# bikealarm.net
KiCad netlist of a schematic drawn in EAGLE
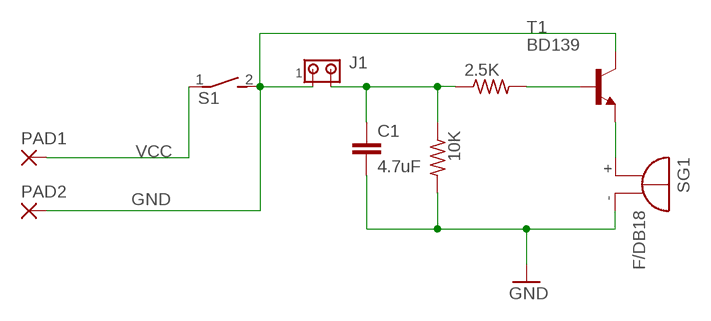
[diagram p0: schematic, sheet 1]

(export (version "E")
  (design (tool "Eeschema 10.0.6"))
  (components
    (comp (ref "2.5K")
      (value "R-US_0204/7")
      (footprint "eagle-import:0204_7")
      (libsource (lib "eagle-import") (part "R-US_0204/7"))
    )
    (comp (ref "10K")
      (value "R-US_0204/7")
      (footprint "eagle-import:0204_7")
      (libsource (lib "eagle-import") (part "R-US_0204/7"))
    )
    (comp (ref "C1")
      (value "4.7uF")
      (footprint "eagle-import:C025-030X050")
      (libsource (lib "eagle-import") (part "C-EU025-030X050"))
    )
    (comp (ref "J1")
      (value "MTA02-156")
      (footprint "eagle-import:1X2MTA")
      (libsource (lib "eagle-import") (part "MTA02-156"))
    )
    (comp (ref "PAD1")
      (value "2,15/1,0")
      (footprint "eagle-import:2,15_1,0")
      (libsource (lib "eagle-import") (part "2,15/1,0"))
    )
    (comp (ref "PAD2")
      (value "2,15/1,0")
      (footprint "eagle-import:2,15_1,0")
      (libsource (lib "eagle-import") (part "2,15/1,0"))
    )
    (comp (ref "S1")
      (value "DS01E")
      (footprint "eagle-import:DS-01")
      (libsource (lib "eagle-import") (part "DS01E"))
    )
    (comp (ref "SG1")
      (value "F/DB18")
      (footprint "eagle-import:F_DB18")
      (libsource (lib "eagle-import") (part "F/DB18"))
    )
    (comp (ref "T1")
      (value "BD139")
      (footprint "eagle-import:TO126")
      (libsource (lib "eagle-import") (part "BD139"))
    )
  )
  (nets
    (net (code "1") (name "/VCC") (class "Default")
      (node (ref "PAD1") (pin "1") (pinfunction "P_1") (pintype "passive"))
      (node (ref "S1") (pin "1") (pinfunction "1_1") (pintype "passive"))
    )
    (net (code "2") (name "GND") (class "Default")
      (node (ref "10K") (pin "2") (pinfunction "2_2") (pintype "passive"))
      (node (ref "C1") (pin "2") (pinfunction "2_2") (pintype "passive"))
      (node (ref "J1") (pin "1") (pinfunction "1_1") (pintype "passive"))
      (node (ref "PAD2") (pin "1") (pinfunction "P_1") (pintype "passive"))
      (node (ref "S1") (pin "2") (pinfunction "2_2") (pintype "passive"))
      (node (ref "SG1") (pin "-") (pinfunction "-_-") (pintype "passive"))
      (node (ref "T1") (pin "2") (pinfunction "C_2") (pintype "passive"))
    )
    (net (code "3") (name "Net-(10K-Pad1)") (class "Default")
      (node (ref "10K") (pin "1") (pinfunction "1_1") (pintype "passive"))
      (node (ref "2.5K") (pin "1") (pinfunction "1_1") (pintype "passive"))
      (node (ref "C1") (pin "1") (pinfunction "1_1") (pintype "passive"))
      (node (ref "J1") (pin "2") (pinfunction "2_2") (pintype "passive"))
    )
    (net (code "4") (name "Net-(T1-B)") (class "Default")
      (node (ref "2.5K") (pin "2") (pinfunction "2_2") (pintype "passive"))
      (node (ref "T1") (pin "3") (pinfunction "B_3") (pintype "passive"))
    )
    (net (code "5") (name "Net-(T1-E)") (class "Default")
      (node (ref "SG1") (pin "+") (pinfunction "+_+") (pintype "passive"))
      (node (ref "T1") (pin "1") (pinfunction "E_1") (pintype "passive"))
    )
  )
)
